# IO.net
KiCad netlist of a schematic drawn in Altium Designer
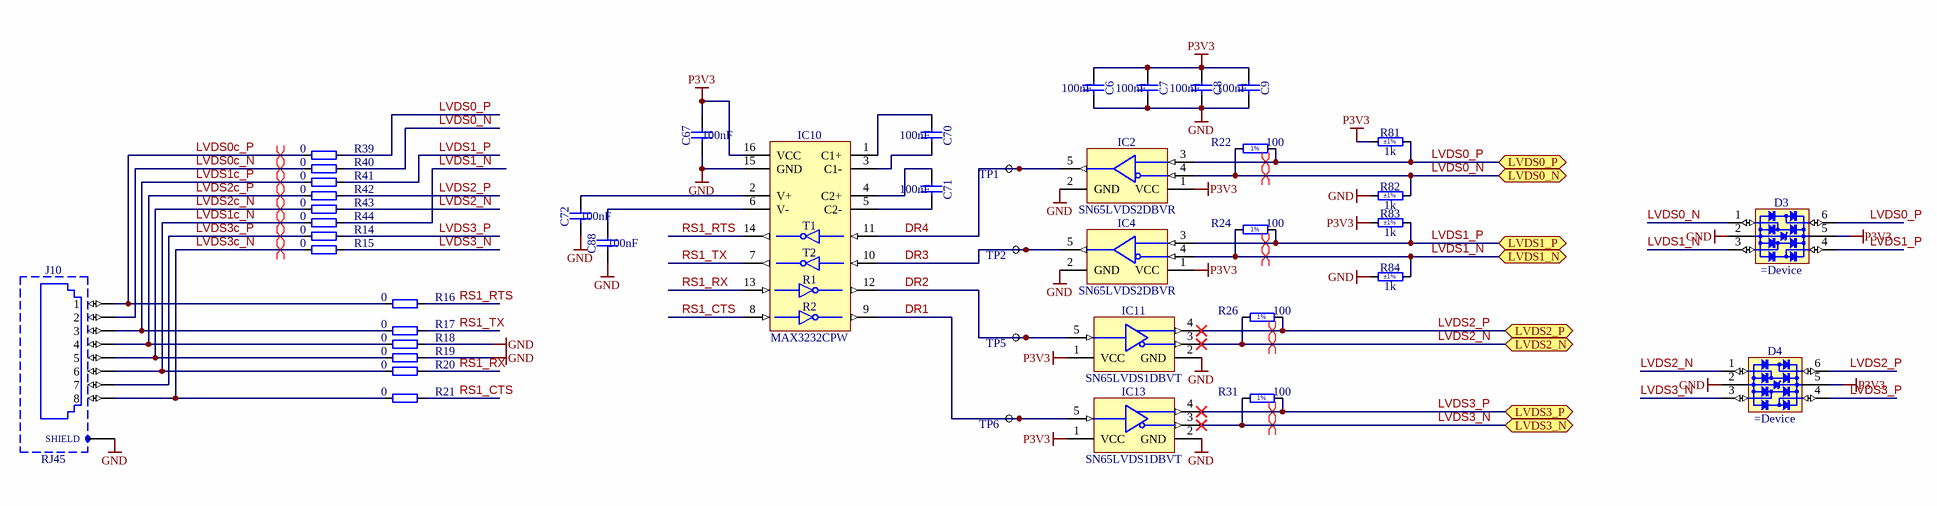
[diagram p0: IO.SchDoc]

(export (version "E")
  (design (tool "Eeschema 10.0.6"))
  (components
    (comp (ref "C6")
      (value "100nF")
      (footprint "CAPC1005X55N")
      (description "Non-polarised capacitor")
      (fields
        (field (name "PART NUMBER") "CC0402_100NF_16V_10%_X5R")
        (field (name "VOLTAGE") "16V")
        (field (name "AUTHOR") "CERN DEM JLC")
      )
      (libsource (lib "Capacitors") (part "Capacitor - non polarized"))
    )
    (comp (ref "C7")
      (value "100nF")
      (footprint "CAPC1005X55N")
      (description "Non-polarised capacitor")
      (fields
        (field (name "PART NUMBER") "CC0402_100NF_16V_10%_X5R")
        (field (name "VOLTAGE") "16V")
        (field (name "AUTHOR") "CERN DEM JLC")
      )
      (libsource (lib "Capacitors") (part "Capacitor - non polarized"))
    )
    (comp (ref "C8")
      (value "100nF")
      (footprint "CAPC1005X55N")
      (description "Non-polarised capacitor")
      (fields
        (field (name "PART NUMBER") "CC0402_100NF_16V_10%_X5R")
        (field (name "VOLTAGE") "16V")
        (field (name "AUTHOR") "CERN DEM JLC")
      )
      (libsource (lib "Capacitors") (part "Capacitor - non polarized"))
    )
    (comp (ref "C9")
      (value "100nF")
      (footprint "CAPC1005X55N")
      (description "Non-polarised capacitor")
      (fields
        (field (name "PART NUMBER") "CC0402_100NF_16V_10%_X5R")
        (field (name "VOLTAGE") "16V")
        (field (name "AUTHOR") "CERN DEM JLC")
      )
      (libsource (lib "Capacitors") (part "Capacitor - non polarized"))
    )
    (comp (ref "C67")
      (value "100nF")
      (footprint "CAPC1005X55N")
      (description "Non-polarised capacitor")
      (fields
        (field (name "PART NUMBER") "CC0402_100NF_16V_10%_X5R")
        (field (name "VOLTAGE") "16V")
        (field (name "AUTHOR") "CERN DEM JLC")
      )
      (libsource (lib "Capacitors") (part "Capacitor - non polarized"))
    )
    (comp (ref "C70")
      (value "100nF")
      (footprint "CAPC1005X55N")
      (description "Non-polarised capacitor")
      (fields
        (field (name "PART NUMBER") "CC0402_100NF_16V_10%_X5R")
        (field (name "VOLTAGE") "16V")
        (field (name "AUTHOR") "CERN DEM JLC")
      )
      (libsource (lib "Capacitors") (part "Capacitor - non polarized"))
    )
    (comp (ref "C71")
      (value "100nF")
      (footprint "CAPC1005X55N")
      (description "Non-polarised capacitor")
      (fields
        (field (name "PART NUMBER") "CC0402_100NF_16V_10%_X5R")
        (field (name "VOLTAGE") "16V")
        (field (name "AUTHOR") "CERN DEM JLC")
      )
      (libsource (lib "Capacitors") (part "Capacitor - non polarized"))
    )
    (comp (ref "C72")
      (value "100nF")
      (footprint "CAPC1005X55N")
      (description "Non-polarised capacitor")
      (fields
        (field (name "PART NUMBER") "CC0402_100NF_16V_10%_X5R")
        (field (name "VOLTAGE") "16V")
        (field (name "AUTHOR") "CERN DEM JLC")
      )
      (libsource (lib "Capacitors") (part "Capacitor - non polarized"))
    )
    (comp (ref "C88")
      (value "100nF")
      (footprint "CAPC1005X55N")
      (description "Non-polarised capacitor")
      (fields
        (field (name "PART NUMBER") "CC0402_100NF_16V_10%_X5R")
        (field (name "VOLTAGE") "16V")
        (field (name "AUTHOR") "CERN DEM JLC")
      )
      (libsource (lib "Capacitors") (part "Capacitor - non polarized"))
    )
    (comp (ref "D3")
      (value "~")
      (footprint "SOTFL50P160X60-6N")
      (fields (field (name "PART NUMBER") "NUP4114UPXV6T1G"))
      (libsource (lib "ICs And Semiconductors") (part "NUP4114"))
    )
    (comp (ref "D4")
      (value "~")
      (footprint "SOTFL50P160X60-6N")
      (fields (field (name "PART NUMBER") "NUP4114UPXV6T1G"))
      (libsource (lib "ICs And Semiconductors") (part "NUP4114"))
    )
    (comp (ref "IC2")
      (value "SN65LVDS2DBVR")
      (footprint "SOT95P280X145-5N")
      (description "High-Speed Differential Line Receiver")
      (fields (field (name "MANUFACTURER") "TEXAS INSTRUMENTS") (field (name "AUTHOR") "CERN DEM JLC"))
      (libsource (lib "ICs And Semiconductors") (part "SN65LVDS2DBV"))
    )
    (comp (ref "IC4")
      (value "SN65LVDS2DBVR")
      (footprint "SOT95P280X145-5N")
      (description "High-Speed Differential Line Receiver")
      (fields (field (name "MANUFACTURER") "TEXAS INSTRUMENTS") (field (name "AUTHOR") "CERN DEM JLC"))
      (libsource (lib "ICs And Semiconductors") (part "SN65LVDS2DBV"))
    )
    (comp (ref "IC10")
      (value "MAX3232CPW")
      (footprint "SOP65P640X120-16N")
      (description "3-V To 5.5-V Multichannel RS-232 Line Driver/Receiver With ±15kV IEC ESD Protection")
      (fields (field (name "MANUFACTURER") "TEXAS INSTRUMENTS") (field (name "AUTHOR") "CERN DEM JLC"))
      (libsource (lib "ICs And Semiconductors") (part "MAX3232CPW"))
    )
    (comp (ref "IC11")
      (value "SN65LVDS1DBVT")
      (footprint "SOT95P280X145-5N")
      (description "High-Speed Differential Line Driver")
      (fields (field (name "MANUFACTURER") "TEXAS INSTRUMENTS") (field (name "AUTHOR") "CERN DEM JLC"))
      (libsource (lib "ICs And Semiconductors") (part "SN65LVDS1DBV"))
    )
    (comp (ref "IC13")
      (value "SN65LVDS1DBVT")
      (footprint "SOT95P280X145-5N")
      (description "High-Speed Differential Line Driver")
      (fields (field (name "MANUFACTURER") "TEXAS INSTRUMENTS") (field (name "AUTHOR") "CERN DEM JLC"))
      (libsource (lib "ICs And Semiconductors") (part "SN65LVDS1DBV"))
    )
    (comp (ref "J10")
      (value "RJ45")
      (footprint "FCI_95678-001LF")
      (description "1 Port, 8 Positions Shielded Snap PEG, CAT5 RJ45 Horizontal Modular Jack")
      (fields
        (field (name "PART NUMBER") "FCI_95678-001LF")
        (field (name "MANUFACTURER") "FCI")
        (field (name "AUTHOR") "CERN DEM BC")
      )
      (libsource (lib "Connectors") (part "FCI_95678-001LF"))
    )
    (comp (ref "R14")
      (value "0")
      (footprint "RESC1005X40N")
      (description "Resistor")
      (fields
        (field (name "PART NUMBER") "R0402_0R_JUMPER")
        (field (name "MANUFACTURER") "GENERIC")
        (field (name "AUTHOR") "CERN DEM JLC")
      )
      (libsource (lib "Resistors") (part "Resistor"))
    )
    (comp (ref "R15")
      (value "0")
      (footprint "RESC1005X40N")
      (description "Resistor")
      (fields
        (field (name "PART NUMBER") "R0402_0R_JUMPER")
        (field (name "MANUFACTURER") "GENERIC")
        (field (name "AUTHOR") "CERN DEM JLC")
      )
      (libsource (lib "Resistors") (part "Resistor"))
    )
    (comp (ref "R16")
      (value "0")
      (footprint "RESC1005X40N")
      (description "Resistor")
      (fields
        (field (name "PART NUMBER") "R0402_0R_JUMPER")
        (field (name "MANUFACTURER") "GENERIC")
        (field (name "AUTHOR") "CERN DEM JLC")
      )
      (libsource (lib "Resistors") (part "Resistor"))
    )
    (comp (ref "R17")
      (value "0")
      (footprint "RESC1005X40N")
      (description "Resistor")
      (fields
        (field (name "PART NUMBER") "R0402_0R_JUMPER")
        (field (name "MANUFACTURER") "GENERIC")
        (field (name "AUTHOR") "CERN DEM JLC")
      )
      (libsource (lib "Resistors") (part "Resistor"))
    )
    (comp (ref "R18")
      (value "0")
      (footprint "RESC1005X40N")
      (description "Resistor")
      (fields
        (field (name "PART NUMBER") "R0402_0R_JUMPER")
        (field (name "MANUFACTURER") "GENERIC")
        (field (name "AUTHOR") "CERN DEM JLC")
      )
      (libsource (lib "Resistors") (part "Resistor"))
    )
    (comp (ref "R19")
      (value "0")
      (footprint "RESC1005X40N")
      (description "Resistor")
      (fields
        (field (name "PART NUMBER") "R0402_0R_JUMPER")
        (field (name "MANUFACTURER") "GENERIC")
        (field (name "AUTHOR") "CERN DEM JLC")
      )
      (libsource (lib "Resistors") (part "Resistor"))
    )
    (comp (ref "R20")
      (value "0")
      (footprint "RESC1005X40N")
      (description "Resistor")
      (fields
        (field (name "PART NUMBER") "R0402_0R_JUMPER")
        (field (name "MANUFACTURER") "GENERIC")
        (field (name "AUTHOR") "CERN DEM JLC")
      )
      (libsource (lib "Resistors") (part "Resistor"))
    )
    (comp (ref "R21")
      (value "0")
      (footprint "RESC1005X40N")
      (description "Resistor")
      (fields
        (field (name "PART NUMBER") "R0402_0R_JUMPER")
        (field (name "MANUFACTURER") "GENERIC")
        (field (name "AUTHOR") "CERN DEM JLC")
      )
      (libsource (lib "Resistors") (part "Resistor"))
    )
    (comp (ref "R22")
      (value "100")
      (footprint "RESC1005X40N")
      (description "Resistor - 1%")
      (fields
        (field (name "PART NUMBER") "R0402_100R_1%_0.0625W_100PPM")
        (field (name "POWER") "0.0625W")
        (field (name "AUTHOR") "CERN DEM JLC")
      )
      (libsource (lib "Resistors") (part "Resistor - 1%"))
    )
    (comp (ref "R24")
      (value "100")
      (footprint "RESC1005X40N")
      (description "Resistor - 1%")
      (fields
        (field (name "PART NUMBER") "R0402_100R_1%_0.0625W_100PPM")
        (field (name "POWER") "0.0625W")
        (field (name "AUTHOR") "CERN DEM JLC")
      )
      (libsource (lib "Resistors") (part "Resistor - 1%"))
    )
    (comp (ref "R26")
      (value "100")
      (footprint "RESC1005X40N")
      (description "Resistor - 1%")
      (fields
        (field (name "PART NUMBER") "R0402_100R_1%_0.0625W_100PPM")
        (field (name "POWER") "0.0625W")
        (field (name "AUTHOR") "CERN DEM JLC")
      )
      (libsource (lib "Resistors") (part "Resistor - 1%"))
    )
    (comp (ref "R31")
      (value "100")
      (footprint "RESC1005X40N")
      (description "Resistor - 1%")
      (fields
        (field (name "PART NUMBER") "R0402_100R_1%_0.0625W_100PPM")
        (field (name "POWER") "0.0625W")
        (field (name "AUTHOR") "CERN DEM JLC")
      )
      (libsource (lib "Resistors") (part "Resistor - 1%"))
    )
    (comp (ref "R39")
      (value "0")
      (footprint "RESC1005X40N")
      (description "Resistor")
      (fields
        (field (name "PART NUMBER") "R0402_0R_JUMPER")
        (field (name "MANUFACTURER") "GENERIC")
        (field (name "AUTHOR") "CERN DEM JLC")
      )
      (libsource (lib "Resistors") (part "Resistor"))
    )
    (comp (ref "R40")
      (value "0")
      (footprint "RESC1005X40N")
      (description "Resistor")
      (fields
        (field (name "PART NUMBER") "R0402_0R_JUMPER")
        (field (name "MANUFACTURER") "GENERIC")
        (field (name "AUTHOR") "CERN DEM JLC")
      )
      (libsource (lib "Resistors") (part "Resistor"))
    )
    (comp (ref "R41")
      (value "0")
      (footprint "RESC1005X40N")
      (description "Resistor")
      (fields
        (field (name "PART NUMBER") "R0402_0R_JUMPER")
        (field (name "MANUFACTURER") "GENERIC")
        (field (name "AUTHOR") "CERN DEM JLC")
      )
      (libsource (lib "Resistors") (part "Resistor"))
    )
    (comp (ref "R42")
      (value "0")
      (footprint "RESC1005X40N")
      (description "Resistor")
      (fields
        (field (name "PART NUMBER") "R0402_0R_JUMPER")
        (field (name "MANUFACTURER") "GENERIC")
        (field (name "AUTHOR") "CERN DEM JLC")
      )
      (libsource (lib "Resistors") (part "Resistor"))
    )
    (comp (ref "R43")
      (value "0")
      (footprint "RESC1005X40N")
      (description "Resistor")
      (fields
        (field (name "PART NUMBER") "R0402_0R_JUMPER")
        (field (name "MANUFACTURER") "GENERIC")
        (field (name "AUTHOR") "CERN DEM JLC")
      )
      (libsource (lib "Resistors") (part "Resistor"))
    )
    (comp (ref "R44")
      (value "0")
      (footprint "RESC1005X40N")
      (description "Resistor")
      (fields
        (field (name "PART NUMBER") "R0402_0R_JUMPER")
        (field (name "MANUFACTURER") "GENERIC")
        (field (name "AUTHOR") "CERN DEM JLC")
      )
      (libsource (lib "Resistors") (part "Resistor"))
    )
    (comp (ref "R81")
      (value "1k")
      (footprint "RESC1005X40N")
      (description "Resistor - 1%")
      (fields
        (field (name "TOLERANCE") "±1%")
        (field (name "PART NUMBER") "R0402_1K_1%_0.0625W_100PPM")
        (field (name "POWER") "0.0625W")
        (field (name "AUTHOR") "CERN DEM JLC")
      )
      (libsource (lib "Resistors") (part "Resistor - 1%"))
    )
    (comp (ref "R82")
      (value "1k")
      (footprint "RESC1005X40N")
      (description "Resistor - 1%")
      (fields
        (field (name "TOLERANCE") "±1%")
        (field (name "PART NUMBER") "R0402_1K_1%_0.0625W_100PPM")
        (field (name "POWER") "0.0625W")
        (field (name "AUTHOR") "CERN DEM JLC")
      )
      (libsource (lib "Resistors") (part "Resistor - 1%"))
    )
    (comp (ref "R83")
      (value "1k")
      (footprint "RESC1005X40N")
      (description "Resistor - 1%")
      (fields
        (field (name "TOLERANCE") "±1%")
        (field (name "PART NUMBER") "R0402_1K_1%_0.0625W_100PPM")
        (field (name "POWER") "0.0625W")
        (field (name "AUTHOR") "CERN DEM JLC")
      )
      (libsource (lib "Resistors") (part "Resistor - 1%"))
    )
    (comp (ref "R84")
      (value "1k")
      (footprint "RESC1005X40N")
      (description "Resistor - 1%")
      (fields
        (field (name "TOLERANCE") "±1%")
        (field (name "PART NUMBER") "R0402_1K_1%_0.0625W_100PPM")
        (field (name "POWER") "0.0625W")
        (field (name "AUTHOR") "CERN DEM JLC")
      )
      (libsource (lib "Resistors") (part "Resistor - 1%"))
    )
    (comp (ref "TP1")
      (value "TP")
      (footprint "TP")
      (description "Testpoint")
      (libsource (lib "LIBRARY_SCH") (part "TP"))
    )
    (comp (ref "TP2")
      (value "TP")
      (footprint "TP")
      (description "Testpoint")
      (libsource (lib "LIBRARY_SCH") (part "TP"))
    )
    (comp (ref "TP5")
      (value "TP")
      (footprint "TP")
      (description "Testpoint")
      (libsource (lib "LIBRARY_SCH") (part "TP"))
    )
    (comp (ref "TP6")
      (value "TP")
      (footprint "TP")
      (description "Testpoint")
      (libsource (lib "LIBRARY_SCH") (part "TP"))
    )
  )
  (nets
    (net (code "1") (name "/DR1") (class "Default")
      (node (ref "IC10") (pin "9") (pinfunction "R2OUT_9") (pintype "output"))
      (node (ref "IC13") (pin "5") (pinfunction "R_5") (pintype "input"))
      (node (ref "TP6") (pin "1") (pintype "passive"))
    )
    (net (code "2") (name "/DR2") (class "Default")
      (node (ref "IC10") (pin "12") (pinfunction "R1OUT_12") (pintype "output"))
      (node (ref "IC11") (pin "5") (pinfunction "R_5") (pintype "input"))
      (node (ref "TP5") (pin "1") (pintype "passive"))
    )
    (net (code "3") (name "/DR3") (class "Default")
      (node (ref "IC10") (pin "10") (pinfunction "T2IN_10") (pintype "input"))
      (node (ref "IC4") (pin "5") (pinfunction "R_5") (pintype "output"))
      (node (ref "TP2") (pin "1") (pintype "passive"))
    )
    (net (code "4") (name "/DR4") (class "Default")
      (node (ref "IC10") (pin "11") (pinfunction "T1IN_11") (pintype "input"))
      (node (ref "IC2") (pin "5") (pinfunction "R_5") (pintype "output"))
      (node (ref "TP1") (pin "1") (pintype "passive"))
    )
    (net (code "5") (name "/LVDS0_N") (class "Default")
      (node (ref "D3") (pin "1") (pinfunction "I/O1_1") (pintype "bidirectional"))
      (node (ref "IC2") (pin "4") (pinfunction "B_4") (pintype "input"))
      (node (ref "R22") (pin "1") (pinfunction "1_1") (pintype "passive"))
      (node (ref "R40") (pin "2") (pinfunction "2_2") (pintype "passive"))
      (node (ref "R82") (pin "2") (pinfunction "2_2") (pintype "passive"))
    )
    (net (code "6") (name "/LVDS0_P") (class "Default")
      (node (ref "D3") (pin "6") (pinfunction "I/O4_6") (pintype "bidirectional"))
      (node (ref "IC2") (pin "3") (pinfunction "A_3") (pintype "input"))
      (node (ref "R22") (pin "2") (pinfunction "2_2") (pintype "passive"))
      (node (ref "R39") (pin "2") (pinfunction "2_2") (pintype "passive"))
      (node (ref "R81") (pin "2") (pinfunction "2_2") (pintype "passive"))
    )
    (net (code "7") (name "/LVDS0c_N") (class "Default")
      (node (ref "J10") (pin "2") (pinfunction "2_2") (pintype "bidirectional"))
      (node (ref "R40") (pin "1") (pinfunction "1_1") (pintype "passive"))
    )
    (net (code "8") (name "/LVDS0c_P") (class "Default")
      (node (ref "J10") (pin "1") (pinfunction "1_1") (pintype "bidirectional"))
      (node (ref "R16") (pin "1") (pinfunction "1_1") (pintype "passive"))
      (node (ref "R39") (pin "1") (pinfunction "1_1") (pintype "passive"))
    )
    (net (code "9") (name "/LVDS1_N") (class "Default")
      (node (ref "D3") (pin "3") (pinfunction "I/O2_3") (pintype "bidirectional"))
      (node (ref "IC4") (pin "4") (pinfunction "B_4") (pintype "input"))
      (node (ref "R24") (pin "1") (pinfunction "1_1") (pintype "passive"))
      (node (ref "R44") (pin "2") (pinfunction "2_2") (pintype "passive"))
      (node (ref "R84") (pin "2") (pinfunction "2_2") (pintype "passive"))
    )
    (net (code "10") (name "/LVDS1_P") (class "Default")
      (node (ref "D3") (pin "4") (pinfunction "I/O3_4") (pintype "bidirectional"))
      (node (ref "IC4") (pin "3") (pinfunction "A_3") (pintype "input"))
      (node (ref "R24") (pin "2") (pinfunction "2_2") (pintype "passive"))
      (node (ref "R41") (pin "2") (pinfunction "2_2") (pintype "passive"))
      (node (ref "R83") (pin "2") (pinfunction "2_2") (pintype "passive"))
    )
    (net (code "11") (name "/LVDS1c_N") (class "Default")
      (node (ref "J10") (pin "6") (pinfunction "6_6") (pintype "bidirectional"))
      (node (ref "R20") (pin "1") (pinfunction "1_1") (pintype "passive"))
      (node (ref "R44") (pin "1") (pinfunction "1_1") (pintype "passive"))
    )
    (net (code "12") (name "/LVDS1c_P") (class "Default")
      (node (ref "J10") (pin "3") (pinfunction "3_3") (pintype "bidirectional"))
      (node (ref "R17") (pin "1") (pinfunction "1_1") (pintype "passive"))
      (node (ref "R41") (pin "1") (pinfunction "1_1") (pintype "passive"))
    )
    (net (code "13") (name "/LVDS2_N") (class "Default")
      (node (ref "D4") (pin "1") (pinfunction "I/O1_1") (pintype "bidirectional"))
      (node (ref "IC11") (pin "3") (pinfunction "A_3") (pintype "output"))
      (node (ref "R26") (pin "1") (pinfunction "1_1") (pintype "passive"))
      (node (ref "R43") (pin "2") (pinfunction "2_2") (pintype "passive"))
    )
    (net (code "14") (name "/LVDS2_P") (class "Default")
      (node (ref "D4") (pin "6") (pinfunction "I/O4_6") (pintype "bidirectional"))
      (node (ref "IC11") (pin "4") (pinfunction "B_4") (pintype "output"))
      (node (ref "R26") (pin "2") (pinfunction "2_2") (pintype "passive"))
      (node (ref "R42") (pin "2") (pinfunction "2_2") (pintype "passive"))
    )
    (net (code "15") (name "/LVDS2c_N") (class "Default")
      (node (ref "J10") (pin "5") (pinfunction "5_5") (pintype "bidirectional"))
      (node (ref "R19") (pin "1") (pinfunction "1_1") (pintype "passive"))
      (node (ref "R43") (pin "1") (pinfunction "1_1") (pintype "passive"))
    )
    (net (code "16") (name "/LVDS2c_P") (class "Default")
      (node (ref "J10") (pin "4") (pinfunction "4_4") (pintype "bidirectional"))
      (node (ref "R18") (pin "1") (pinfunction "1_1") (pintype "passive"))
      (node (ref "R42") (pin "1") (pinfunction "1_1") (pintype "passive"))
    )
    (net (code "17") (name "/LVDS3_N") (class "Default")
      (node (ref "D4") (pin "3") (pinfunction "I/O2_3") (pintype "bidirectional"))
      (node (ref "IC13") (pin "3") (pinfunction "A_3") (pintype "output"))
      (node (ref "R15") (pin "2") (pinfunction "2_2") (pintype "passive"))
      (node (ref "R31") (pin "1") (pinfunction "1_1") (pintype "passive"))
    )
    (net (code "18") (name "/LVDS3_P") (class "Default")
      (node (ref "D4") (pin "4") (pinfunction "I/O3_4") (pintype "bidirectional"))
      (node (ref "IC13") (pin "4") (pinfunction "B_4") (pintype "output"))
      (node (ref "R14") (pin "2") (pinfunction "2_2") (pintype "passive"))
      (node (ref "R31") (pin "2") (pinfunction "2_2") (pintype "passive"))
    )
    (net (code "19") (name "/LVDS3c_N") (class "Default")
      (node (ref "J10") (pin "8") (pinfunction "8_8") (pintype "bidirectional"))
      (node (ref "R15") (pin "1") (pinfunction "1_1") (pintype "passive"))
      (node (ref "R21") (pin "1") (pinfunction "1_1") (pintype "passive"))
    )
    (net (code "20") (name "/LVDS3c_P") (class "Default")
      (node (ref "J10") (pin "7") (pinfunction "7_7") (pintype "bidirectional"))
      (node (ref "R14") (pin "1") (pinfunction "1_1") (pintype "passive"))
    )
    (net (code "21") (name "/RS1_CTS") (class "Default")
      (node (ref "IC10") (pin "8") (pinfunction "R2IN_8") (pintype "input"))
      (node (ref "R21") (pin "2") (pinfunction "2_2") (pintype "passive"))
    )
    (net (code "22") (name "/RS1_RTS") (class "Default")
      (node (ref "IC10") (pin "14") (pinfunction "T1OUT_14") (pintype "output"))
      (node (ref "R16") (pin "2") (pinfunction "2_2") (pintype "passive"))
    )
    (net (code "23") (name "/RS1_RX") (class "Default")
      (node (ref "IC10") (pin "13") (pinfunction "R1IN_13") (pintype "input"))
      (node (ref "R20") (pin "2") (pinfunction "2_2") (pintype "passive"))
    )
    (net (code "24") (name "/RS1_TX") (class "Default")
      (node (ref "IC10") (pin "7") (pinfunction "T2OUT_7") (pintype "output"))
      (node (ref "R17") (pin "2") (pinfunction "2_2") (pintype "passive"))
    )
    (net (code "25") (name "GND") (class "Default")
      (node (ref "C6") (pin "1") (pinfunction "1_1") (pintype "passive"))
      (node (ref "C67") (pin "1") (pinfunction "1_1") (pintype "passive"))
      (node (ref "C7") (pin "1") (pinfunction "1_1") (pintype "passive"))
      (node (ref "C72") (pin "2") (pinfunction "2_2") (pintype "passive"))
      (node (ref "C8") (pin "1") (pinfunction "1_1") (pintype "passive"))
      (node (ref "C88") (pin "2") (pinfunction "2_2") (pintype "passive"))
      (node (ref "C9") (pin "1") (pinfunction "1_1") (pintype "passive"))
      (node (ref "D3") (pin "2") (pinfunction "GND_2") (pintype "power_in"))
      (node (ref "D4") (pin "2") (pinfunction "GND_2") (pintype "power_in"))
      (node (ref "IC10") (pin "15") (pinfunction "GND_15") (pintype "power_in"))
      (node (ref "IC11") (pin "2") (pinfunction "GND_2") (pintype "power_in"))
      (node (ref "IC13") (pin "2") (pinfunction "GND_2") (pintype "power_in"))
      (node (ref "IC2") (pin "2") (pinfunction "GND_2") (pintype "power_in"))
      (node (ref "IC4") (pin "2") (pinfunction "GND_2") (pintype "power_in"))
      (node (ref "J10") (pin "SHIELD") (pinfunction "SHIELD_SHIELD") (pintype "passive"))
      (node (ref "R18") (pin "2") (pinfunction "2_2") (pintype "passive"))
      (node (ref "R19") (pin "2") (pinfunction "2_2") (pintype "passive"))
      (node (ref "R82") (pin "1") (pinfunction "1_1") (pintype "passive"))
      (node (ref "R84") (pin "1") (pinfunction "1_1") (pintype "passive"))
    )
    (net (code "26") (name "Net-(IC10-C1+)") (class "Default")
      (node (ref "C70") (pin "2") (pinfunction "2_2") (pintype "passive"))
      (node (ref "IC10") (pin "1") (pinfunction "C1+_1") (pintype "passive"))
    )
    (net (code "27") (name "Net-(IC10-C1-)") (class "Default")
      (node (ref "C70") (pin "1") (pinfunction "1_1") (pintype "passive"))
      (node (ref "IC10") (pin "3") (pinfunction "C1-_3") (pintype "passive"))
    )
    (net (code "28") (name "Net-(IC10-C2+)") (class "Default")
      (node (ref "C71") (pin "2") (pinfunction "2_2") (pintype "passive"))
      (node (ref "IC10") (pin "4") (pinfunction "C2+_4") (pintype "passive"))
    )
    (net (code "29") (name "Net-(IC10-C2-)") (class "Default")
      (node (ref "C71") (pin "1") (pinfunction "1_1") (pintype "passive"))
      (node (ref "IC10") (pin "5") (pinfunction "C2-_5") (pintype "passive"))
    )
    (net (code "30") (name "Net-(IC10-V+)") (class "Default")
      (node (ref "C72") (pin "1") (pinfunction "1_1") (pintype "passive"))
      (node (ref "IC10") (pin "2") (pinfunction "V+_2") (pintype "power_in"))
    )
    (net (code "31") (name "Net-(IC10-V-)") (class "Default")
      (node (ref "C88") (pin "1") (pinfunction "1_1") (pintype "passive"))
      (node (ref "IC10") (pin "6") (pinfunction "V-_6") (pintype "power_in"))
    )
    (net (code "32") (name "P3V3") (class "Default")
      (node (ref "C6") (pin "2") (pinfunction "2_2") (pintype "passive"))
      (node (ref "C67") (pin "2") (pinfunction "2_2") (pintype "passive"))
      (node (ref "C7") (pin "2") (pinfunction "2_2") (pintype "passive"))
      (node (ref "C8") (pin "2") (pinfunction "2_2") (pintype "passive"))
      (node (ref "C9") (pin "2") (pinfunction "2_2") (pintype "passive"))
      (node (ref "D3") (pin "5") (pinfunction "VBUS_5") (pintype "power_in"))
      (node (ref "D4") (pin "5") (pinfunction "VBUS_5") (pintype "power_in"))
      (node (ref "IC10") (pin "16") (pinfunction "VCC_16") (pintype "power_in"))
      (node (ref "IC11") (pin "1") (pinfunction "VCC_1") (pintype "power_in"))
      (node (ref "IC13") (pin "1") (pinfunction "VCC_1") (pintype "power_in"))
      (node (ref "IC2") (pin "1") (pinfunction "VCC_1") (pintype "power_in"))
      (node (ref "IC4") (pin "1") (pinfunction "VCC_1") (pintype "power_in"))
      (node (ref "R81") (pin "1") (pinfunction "1_1") (pintype "passive"))
      (node (ref "R83") (pin "1") (pinfunction "1_1") (pintype "passive"))
    )
  )
)
